# with_boost.net
KiCad netlist of a schematic drawn in EAGLE
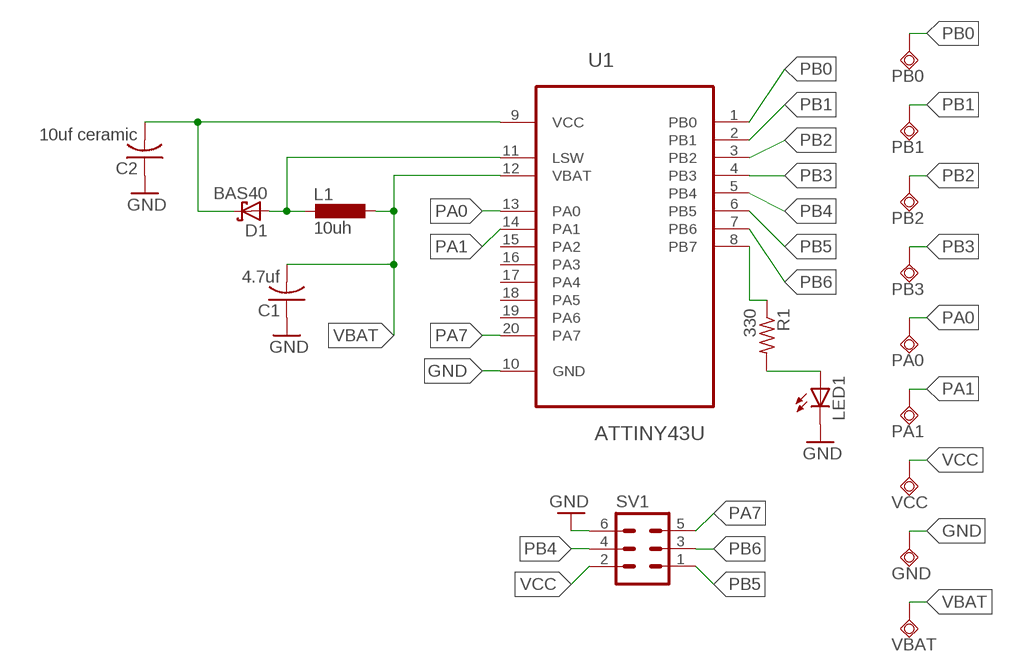
[diagram p0: schematic, sheet 1]

(export (version "E")
  (design (tool "Eeschema 10.0.6"))
  (components
    (comp (ref "C1")
      (value "4.7uf")
      (footprint "eagle-import:C1206K")
      (libsource (lib "eagle-import") (part "C-USC1206K"))
    )
    (comp (ref "C2")
      (value "10uf ceramic")
      (footprint "eagle-import:C1206K")
      (libsource (lib "eagle-import") (part "C-USC1206K"))
    )
    (comp (ref "D1")
      (value "BAS40")
      (footprint "eagle-import:SOT23")
      (libsource (lib "eagle-import") (part "BAS40"))
    )
    (comp (ref "GND")
      (value "TPSQTP20SQ")
      (footprint "eagle-import:TP20SQ")
      (libsource (lib "eagle-import") (part "TPSQTP20SQ"))
    )
    (comp (ref "L1")
      (value "10uh")
      (footprint "eagle-import:L3225M")
      (libsource (lib "eagle-import") (part "L-EUL3225M"))
    )
    (comp (ref "LED1")
      (value "LEDCHIPLED_1206")
      (footprint "eagle-import:CHIPLED_1206")
      (libsource (lib "eagle-import") (part "LEDCHIPLED_1206"))
    )
    (comp (ref "PA0")
      (value "TPSQTP20SQ")
      (footprint "eagle-import:TP20SQ")
      (libsource (lib "eagle-import") (part "TPSQTP20SQ"))
    )
    (comp (ref "PA1")
      (value "TPSQTP20SQ")
      (footprint "eagle-import:TP20SQ")
      (libsource (lib "eagle-import") (part "TPSQTP20SQ"))
    )
    (comp (ref "PB0")
      (value "TPSQTP20SQ")
      (footprint "eagle-import:TP20SQ")
      (libsource (lib "eagle-import") (part "TPSQTP20SQ"))
    )
    (comp (ref "PB1")
      (value "TPSQTP20SQ")
      (footprint "eagle-import:TP20SQ")
      (libsource (lib "eagle-import") (part "TPSQTP20SQ"))
    )
    (comp (ref "PB2")
      (value "TPSQTP20SQ")
      (footprint "eagle-import:TP20SQ")
      (libsource (lib "eagle-import") (part "TPSQTP20SQ"))
    )
    (comp (ref "PB3")
      (value "TPSQTP20SQ")
      (footprint "eagle-import:TP20SQ")
      (libsource (lib "eagle-import") (part "TPSQTP20SQ"))
    )
    (comp (ref "R1")
      (value "330")
      (footprint "eagle-import:M1206")
      (libsource (lib "eagle-import") (part "R-US_M1206"))
    )
    (comp (ref "SV1")
      (value "MA03-2")
      (footprint "eagle-import:MA03-2")
      (libsource (lib "eagle-import") (part "MA03-2"))
    )
    (comp (ref "U1")
      (value "ATTINY43U")
      (footprint "eagle-import:SOIC127P1032X265-20N")
      (fields (field (name "MPN") "ATTINY43U-SU"))
      (libsource (lib "eagle-import") (part "ATTINY43U-SU"))
    )
    (comp (ref "VBAT")
      (value "TPSQTP20SQ")
      (footprint "eagle-import:TP20SQ")
      (libsource (lib "eagle-import") (part "TPSQTP20SQ"))
    )
    (comp (ref "VCC")
      (value "TPSQTP20SQ")
      (footprint "eagle-import:TP20SQ")
      (libsource (lib "eagle-import") (part "TPSQTP20SQ"))
    )
  )
  (nets
    (net (code "1") (name "GND") (class "Default")
      (node (ref "C1") (pin "1") (pinfunction "1_1") (pintype "passive"))
      (node (ref "C2") (pin "1") (pinfunction "1_1") (pintype "passive"))
      (node (ref "GND") (pin "TP") (pinfunction "TP_TP") (pintype "input"))
      (node (ref "LED1") (pin "C") (pinfunction "C_C") (pintype "passive"))
      (node (ref "SV1") (pin "6") (pinfunction "6_6") (pintype "passive"))
      (node (ref "U1") (pin "10") (pinfunction "GND_10") (pintype "passive"))
    )
    (net (code "2") (name "Net-(D1-A)") (class "Default")
      (node (ref "D1") (pin "1") (pinfunction "A_1") (pintype "passive"))
      (node (ref "L1") (pin "2") (pinfunction "2_2") (pintype "passive"))
      (node (ref "U1") (pin "11") (pinfunction "LSW_11") (pintype "passive"))
    )
    (net (code "3") (name "Net-(LED1-PadA)") (class "Default")
      (node (ref "LED1") (pin "A") (pinfunction "A_A") (pintype "passive"))
      (node (ref "R1") (pin "2") (pinfunction "2_2") (pintype "passive"))
    )
    (net (code "4") (name "Net-(U1-PB7)") (class "Default")
      (node (ref "R1") (pin "1") (pinfunction "1_1") (pintype "passive"))
      (node (ref "U1") (pin "8") (pinfunction "PB7_8") (pintype "bidirectional"))
    )
    (net (code "5") (name "PA0") (class "Default")
      (node (ref "PA0") (pin "TP") (pinfunction "TP_TP") (pintype "input"))
      (node (ref "U1") (pin "13") (pinfunction "PA0_13") (pintype "bidirectional"))
    )
    (net (code "6") (name "PA1") (class "Default")
      (node (ref "PA1") (pin "TP") (pinfunction "TP_TP") (pintype "input"))
      (node (ref "U1") (pin "14") (pinfunction "PA1_14") (pintype "bidirectional"))
    )
    (net (code "7") (name "PA7") (class "Default")
      (node (ref "SV1") (pin "5") (pinfunction "5_5") (pintype "passive"))
      (node (ref "U1") (pin "20") (pinfunction "PA7_20") (pintype "bidirectional"))
    )
    (net (code "8") (name "PB0") (class "Default")
      (node (ref "PB0") (pin "TP") (pinfunction "TP_TP") (pintype "input"))
      (node (ref "U1") (pin "1") (pinfunction "PB0_1") (pintype "bidirectional"))
    )
    (net (code "9") (name "PB1") (class "Default")
      (node (ref "PB1") (pin "TP") (pinfunction "TP_TP") (pintype "input"))
      (node (ref "U1") (pin "2") (pinfunction "PB1_2") (pintype "bidirectional"))
    )
    (net (code "10") (name "PB2") (class "Default")
      (node (ref "PB2") (pin "TP") (pinfunction "TP_TP") (pintype "input"))
      (node (ref "U1") (pin "3") (pinfunction "PB2_3") (pintype "bidirectional"))
    )
    (net (code "11") (name "PB3") (class "Default")
      (node (ref "PB3") (pin "TP") (pinfunction "TP_TP") (pintype "input"))
      (node (ref "U1") (pin "4") (pinfunction "PB3_4") (pintype "bidirectional"))
    )
    (net (code "12") (name "PB4") (class "Default")
      (node (ref "SV1") (pin "4") (pinfunction "4_4") (pintype "passive"))
      (node (ref "U1") (pin "5") (pinfunction "PB4_5") (pintype "bidirectional"))
    )
    (net (code "13") (name "PB5") (class "Default")
      (node (ref "SV1") (pin "1") (pinfunction "1_1") (pintype "passive"))
      (node (ref "U1") (pin "6") (pinfunction "PB5_6") (pintype "bidirectional"))
    )
    (net (code "14") (name "PB6") (class "Default")
      (node (ref "SV1") (pin "3") (pinfunction "3_3") (pintype "passive"))
      (node (ref "U1") (pin "7") (pinfunction "PB6_7") (pintype "bidirectional"))
    )
    (net (code "15") (name "VBAT") (class "Default")
      (node (ref "C1") (pin "2") (pinfunction "2_2") (pintype "passive"))
      (node (ref "L1") (pin "1") (pinfunction "1_1") (pintype "passive"))
      (node (ref "U1") (pin "12") (pinfunction "VBAT_12") (pintype "passive"))
      (node (ref "VBAT") (pin "TP") (pinfunction "TP_TP") (pintype "input"))
    )
    (net (code "16") (name "VCC") (class "Default")
      (node (ref "C2") (pin "2") (pinfunction "2_2") (pintype "passive"))
      (node (ref "D1") (pin "3") (pinfunction "C_3") (pintype "passive"))
      (node (ref "SV1") (pin "2") (pinfunction "2_2") (pintype "passive"))
      (node (ref "U1") (pin "9") (pinfunction "VCC_9") (pintype "power_in"))
      (node (ref "VCC") (pin "TP") (pinfunction "TP_TP") (pintype "input"))
    )
    (net (code "17") (name "unconnected-(U1-PA2-Pad15)") (class "Default")
      (node (ref "U1") (pin "15") (pinfunction "PA2_15") (pintype "bidirectional"))
    )
    (net (code "18") (name "unconnected-(U1-PA3-Pad16)") (class "Default")
      (node (ref "U1") (pin "16") (pinfunction "PA3_16") (pintype "bidirectional"))
    )
    (net (code "19") (name "unconnected-(U1-PA4-Pad17)") (class "Default")
      (node (ref "U1") (pin "17") (pinfunction "PA4_17") (pintype "bidirectional"))
    )
    (net (code "20") (name "unconnected-(U1-PA5-Pad18)") (class "Default")
      (node (ref "U1") (pin "18") (pinfunction "PA5_18") (pintype "bidirectional"))
    )
    (net (code "21") (name "unconnected-(U1-PA6-Pad19)") (class "Default")
      (node (ref "U1") (pin "19") (pinfunction "PA6_19") (pintype "bidirectional"))
    )
  )
)
